# origin.net
KiCad netlist of a schematic drawn in Altium Designer
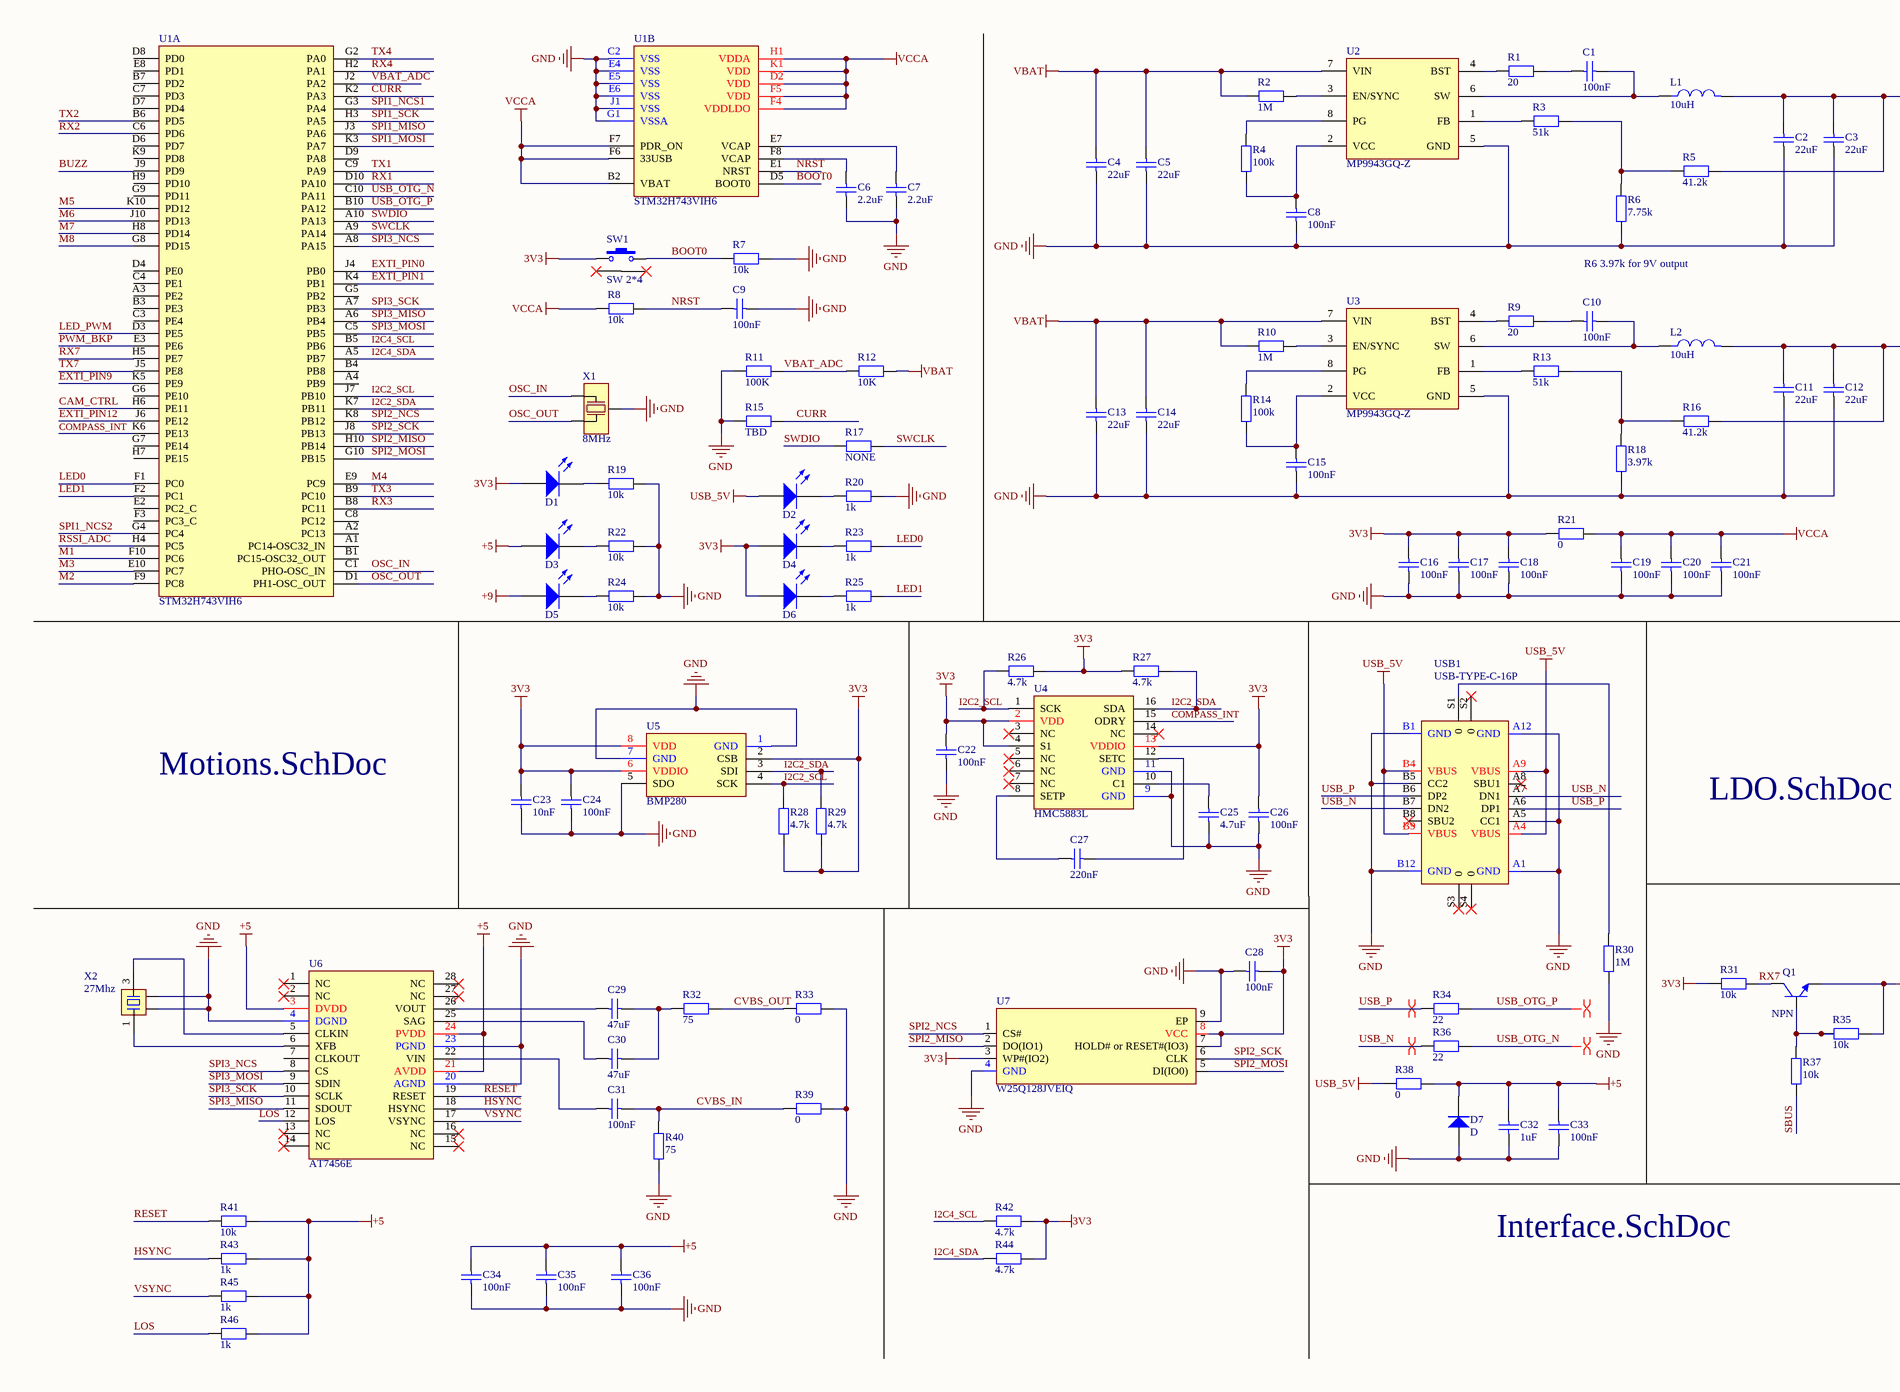
[diagram p0: origin.SchDoc, left]
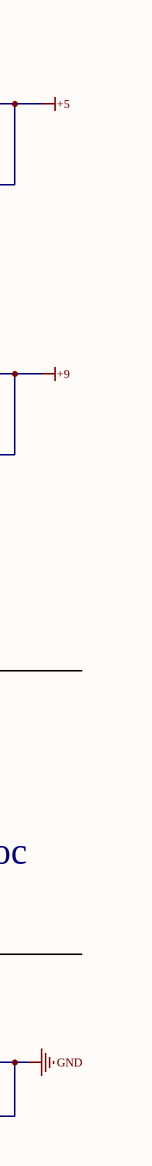
[diagram p1: origin.SchDoc, middle]

(export (version "E")
  (design (tool "Eeschema 10.0.6"))
  (components
    (comp (ref "C1")
      (value "100nF")
      (footprint "C0402_NS")
      (description "Capacitance 0402")
      (libsource (lib "AxisQuad Components Lib") (part "C0402"))
    )
    (comp (ref "C2")
      (value "22uF")
      (footprint "C1206_NS")
      (description "Capacitance 1206")
      (libsource (lib "AxisQuad Components Lib") (part "C1206"))
    )
    (comp (ref "C3")
      (value "22uF")
      (footprint "C1206_NS")
      (description "Capacitance 1206")
      (libsource (lib "AxisQuad Components Lib") (part "C1206"))
    )
    (comp (ref "C4")
      (value "22uF")
      (footprint "C1206_NS")
      (description "Capacitance 1206")
      (libsource (lib "AxisQuad Components Lib") (part "C1206"))
    )
    (comp (ref "C5")
      (value "22uF")
      (footprint "C1206_NS")
      (description "Capacitance 1206")
      (libsource (lib "AxisQuad Components Lib") (part "C1206"))
    )
    (comp (ref "C6")
      (value "2.2uF")
      (footprint "C0402_NS")
      (description "Capacitance 0402")
      (libsource (lib "AxisQuad Components Lib") (part "C0402"))
    )
    (comp (ref "C7")
      (value "2.2uF")
      (footprint "C0402_NS")
      (description "Capacitance 0402")
      (libsource (lib "AxisQuad Components Lib") (part "C0402"))
    )
    (comp (ref "C8")
      (value "100nF")
      (footprint "C0402_NS")
      (description "Capacitance 0402")
      (libsource (lib "AxisQuad Components Lib") (part "C0402"))
    )
    (comp (ref "C9")
      (value "100nF")
      (footprint "C0402_NS")
      (description "Capacitance 0402")
      (libsource (lib "AxisQuad Components Lib") (part "C0402"))
    )
    (comp (ref "C10")
      (value "100nF")
      (footprint "C0402_NS")
      (description "Capacitance 0402")
      (libsource (lib "AxisQuad Components Lib") (part "C0402"))
    )
    (comp (ref "C11")
      (value "22uF")
      (footprint "C1206_NS")
      (description "Capacitance 1206")
      (libsource (lib "AxisQuad Components Lib") (part "C1206"))
    )
    (comp (ref "C12")
      (value "22uF")
      (footprint "C1206_NS")
      (description "Capacitance 1206")
      (libsource (lib "AxisQuad Components Lib") (part "C1206"))
    )
    (comp (ref "C13")
      (value "22uF")
      (footprint "C1206_NS")
      (description "Capacitance 1206")
      (libsource (lib "AxisQuad Components Lib") (part "C1206"))
    )
    (comp (ref "C14")
      (value "22uF")
      (footprint "C1206_NS")
      (description "Capacitance 1206")
      (libsource (lib "AxisQuad Components Lib") (part "C1206"))
    )
    (comp (ref "C15")
      (value "100nF")
      (footprint "C0402_NS")
      (description "Capacitance 0402")
      (libsource (lib "AxisQuad Components Lib") (part "C0402"))
    )
    (comp (ref "C16")
      (value "100nF")
      (footprint "C0402_NS")
      (description "Capacitance 0402")
      (libsource (lib "AxisQuad Components Lib") (part "C0402"))
    )
    (comp (ref "C17")
      (value "100nF")
      (footprint "C0402_NS")
      (description "Capacitance 0402")
      (libsource (lib "AxisQuad Components Lib") (part "C0402"))
    )
    (comp (ref "C18")
      (value "100nF")
      (footprint "C0402_NS")
      (description "Capacitance 0402")
      (libsource (lib "AxisQuad Components Lib") (part "C0402"))
    )
    (comp (ref "C19")
      (value "100nF")
      (footprint "C0402_NS")
      (description "Capacitance 0402")
      (libsource (lib "AxisQuad Components Lib") (part "C0402"))
    )
    (comp (ref "C20")
      (value "100nF")
      (footprint "C0402_NS")
      (description "Capacitance 0402")
      (libsource (lib "AxisQuad Components Lib") (part "C0402"))
    )
    (comp (ref "C21")
      (value "100nF")
      (footprint "C0402_NS")
      (description "Capacitance 0402")
      (libsource (lib "AxisQuad Components Lib") (part "C0402"))
    )
    (comp (ref "C22")
      (value "100nF")
      (footprint "C0402_NS")
      (description "Capacitance 0402")
      (libsource (lib "AxisQuad Components Lib") (part "C0402"))
    )
    (comp (ref "C23")
      (value "10nF")
      (footprint "C0402_NS")
      (description "Capacitance 0402")
      (libsource (lib "AxisQuad Components Lib") (part "C0402"))
    )
    (comp (ref "C24")
      (value "100nF")
      (footprint "C0402_NS")
      (description "Capacitance 0402")
      (libsource (lib "AxisQuad Components Lib") (part "C0402"))
    )
    (comp (ref "C25")
      (value "4.7uF")
      (footprint "C0402_NS")
      (description "Capacitance 0402")
      (libsource (lib "AxisQuad Components Lib") (part "C0402"))
    )
    (comp (ref "C26")
      (value "100nF")
      (footprint "C0402_NS")
      (description "Capacitance 0402")
      (libsource (lib "AxisQuad Components Lib") (part "C0402"))
    )
    (comp (ref "C27")
      (value "220nF")
      (footprint "C0402_NS")
      (description "Capacitance 0402")
      (libsource (lib "AxisQuad Components Lib") (part "C0402"))
    )
    (comp (ref "C28")
      (value "100nF")
      (footprint "C0402_NS")
      (description "Capacitance 0402")
      (libsource (lib "AxisQuad Components Lib") (part "C0402"))
    )
    (comp (ref "C29")
      (value "47uF")
      (footprint "C_3528")
      (libsource (lib "AxisQuad Components Lib") (part "C"))
    )
    (comp (ref "C30")
      (value "47uF")
      (footprint "C_3528")
      (libsource (lib "AxisQuad Components Lib") (part "C"))
    )
    (comp (ref "C31")
      (value "100nF")
      (footprint "C0805_NS")
      (description "Capacitance 0805")
      (libsource (lib "AxisQuad Components Lib") (part "C0805"))
    )
    (comp (ref "C32")
      (value "1uF")
      (footprint "C0402_NS")
      (description "Capacitance 0402")
      (libsource (lib "AxisQuad Components Lib") (part "C0402"))
    )
    (comp (ref "C33")
      (value "100nF")
      (footprint "C0402_NS")
      (description "Capacitance 0402")
      (libsource (lib "AxisQuad Components Lib") (part "C0402"))
    )
    (comp (ref "C34")
      (value "100nF")
      (footprint "C0402_NS")
      (description "Capacitance 0402")
      (libsource (lib "AxisQuad Components Lib") (part "C0402"))
    )
    (comp (ref "C35")
      (value "100nF")
      (footprint "C0402_NS")
      (description "Capacitance 0402")
      (libsource (lib "AxisQuad Components Lib") (part "C0402"))
    )
    (comp (ref "C36")
      (value "100nF")
      (footprint "C0402_NS")
      (description "Capacitance 0402")
      (libsource (lib "AxisQuad Components Lib") (part "C0402"))
    )
    (comp (ref "D1")
      (value "LED")
      (footprint "LED0402-B")
      (description "发光二极管")
      (libsource (lib "AxisQuad Components Lib") (part "LED0402"))
    )
    (comp (ref "D2")
      (value "LED")
      (footprint "LED0402-B")
      (description "发光二极管")
      (libsource (lib "AxisQuad Components Lib") (part "LED0402"))
    )
    (comp (ref "D3")
      (value "LED")
      (footprint "LED0402-B")
      (description "发光二极管")
      (libsource (lib "AxisQuad Components Lib") (part "LED0402"))
    )
    (comp (ref "D4")
      (value "LED")
      (footprint "LED0402-B")
      (description "发光二极管")
      (libsource (lib "AxisQuad Components Lib") (part "LED0402"))
    )
    (comp (ref "D5")
      (value "LED")
      (footprint "LED0402-B")
      (description "发光二极管")
      (libsource (lib "AxisQuad Components Lib") (part "LED0402"))
    )
    (comp (ref "D6")
      (value "LED")
      (footprint "LED0402-B")
      (description "发光二极管")
      (libsource (lib "AxisQuad Components Lib") (part "LED0402"))
    )
    (comp (ref "D7") (value "D") (footprint "SOD-123") (libsource (lib "AxisQuad Components Lib") (part "D")))
    (comp (ref "L1") (value "10uH") (footprint "IHLP2020") (libsource (lib "DBS Components Lib") (part "L")))
    (comp (ref "L2") (value "10uH") (footprint "IHLP2020") (libsource (lib "DBS Components Lib") (part "L")))
    (comp (ref "Q1")
      (value "NPN")
      (footprint "SOT23-3")
      (description "NPN三极管")
      (libsource (lib "AxisQuad Components Lib") (part "NPN"))
    )
    (comp (ref "R1")
      (value "20")
      (footprint "R0402_NS")
      (description "Resistance 0402")
      (libsource (lib "AxisQuad Components Lib") (part "R0402"))
    )
    (comp (ref "R2")
      (value "1M")
      (footprint "R0402_NS")
      (description "Resistance 0402")
      (libsource (lib "AxisQuad Components Lib") (part "R0402"))
    )
    (comp (ref "R3")
      (value "51k")
      (footprint "R0402_NS")
      (description "Resistance 0402")
      (libsource (lib "AxisQuad Components Lib") (part "R0402"))
    )
    (comp (ref "R4")
      (value "100k")
      (footprint "R0402_NS")
      (description "Resistance 0402")
      (libsource (lib "AxisQuad Components Lib") (part "R0402"))
    )
    (comp (ref "R5")
      (value "41.2k")
      (footprint "R0402_NS")
      (description "Resistance 0402")
      (libsource (lib "AxisQuad Components Lib") (part "R0402"))
    )
    (comp (ref "R6")
      (value "7.75k")
      (footprint "R0402_NS")
      (description "Resistance 0402")
      (libsource (lib "AxisQuad Components Lib") (part "R0402"))
    )
    (comp (ref "R7")
      (value "10k")
      (footprint "R0402_NS")
      (description "Resistance 0402")
      (libsource (lib "AxisQuad Components Lib") (part "R0402"))
    )
    (comp (ref "R8")
      (value "10k")
      (footprint "R0402_NS")
      (description "Resistance 0402")
      (libsource (lib "AxisQuad Components Lib") (part "R0402"))
    )
    (comp (ref "R9")
      (value "20")
      (footprint "R0402_NS")
      (description "Resistance 0402")
      (libsource (lib "AxisQuad Components Lib") (part "R0402"))
    )
    (comp (ref "R10")
      (value "1M")
      (footprint "R0402_NS")
      (description "Resistance 0402")
      (libsource (lib "AxisQuad Components Lib") (part "R0402"))
    )
    (comp (ref "R11")
      (value "100K")
      (footprint "R0402_NS")
      (description "Resistance 0402")
      (libsource (lib "AxisQuad Components Lib") (part "R0402"))
    )
    (comp (ref "R12")
      (value "10K")
      (footprint "R0402_NS")
      (description "Resistance 0402")
      (libsource (lib "AxisQuad Components Lib") (part "R0402"))
    )
    (comp (ref "R13")
      (value "51k")
      (footprint "R0402_NS")
      (description "Resistance 0402")
      (libsource (lib "AxisQuad Components Lib") (part "R0402"))
    )
    (comp (ref "R14")
      (value "100k")
      (footprint "R0402_NS")
      (description "Resistance 0402")
      (libsource (lib "AxisQuad Components Lib") (part "R0402"))
    )
    (comp (ref "R15")
      (value "TBD")
      (footprint "R0603_NS")
      (description "Resistance 0603")
      (libsource (lib "DBS Components Lib") (part "R0603"))
    )
    (comp (ref "R16")
      (value "41.2k")
      (footprint "R0402_NS")
      (description "Resistance 0402")
      (libsource (lib "AxisQuad Components Lib") (part "R0402"))
    )
    (comp (ref "R17")
      (value "NONE")
      (footprint "R0402_NS")
      (description "Resistance 0402")
      (libsource (lib "AxisQuad Components Lib") (part "R0402"))
    )
    (comp (ref "R18")
      (value "3.97k")
      (footprint "R0402_NS")
      (description "Resistance 0402")
      (libsource (lib "AxisQuad Components Lib") (part "R0402"))
    )
    (comp (ref "R19")
      (value "10k")
      (footprint "R0402_NS")
      (description "Resistance 0402")
      (libsource (lib "AxisQuad Components Lib") (part "R0402"))
    )
    (comp (ref "R20")
      (value "1k")
      (footprint "R0402_NS")
      (description "Resistance 0402")
      (libsource (lib "AxisQuad Components Lib") (part "R0402"))
    )
    (comp (ref "R21")
      (value "0")
      (footprint "R0402_NS")
      (description "Resistance 0402")
      (libsource (lib "AxisQuad Components Lib") (part "R0402"))
    )
    (comp (ref "R22")
      (value "10k")
      (footprint "R0402_NS")
      (description "Resistance 0402")
      (libsource (lib "AxisQuad Components Lib") (part "R0402"))
    )
    (comp (ref "R23")
      (value "1k")
      (footprint "R0402_NS")
      (description "Resistance 0402")
      (libsource (lib "AxisQuad Components Lib") (part "R0402"))
    )
    (comp (ref "R24")
      (value "10k")
      (footprint "R0402_NS")
      (description "Resistance 0402")
      (libsource (lib "AxisQuad Components Lib") (part "R0402"))
    )
    (comp (ref "R25")
      (value "1k")
      (footprint "R0402_NS")
      (description "Resistance 0402")
      (libsource (lib "AxisQuad Components Lib") (part "R0402"))
    )
    (comp (ref "R26")
      (value "4.7k")
      (footprint "R0402_NS")
      (description "Resistance 0402")
      (libsource (lib "AxisQuad Components Lib") (part "R0402"))
    )
    (comp (ref "R27")
      (value "4.7k")
      (footprint "R0402_NS")
      (description "Resistance 0402")
      (libsource (lib "AxisQuad Components Lib") (part "R0402"))
    )
    (comp (ref "R28")
      (value "4.7k")
      (footprint "R0402_NS")
      (description "Resistance 0402")
      (libsource (lib "AxisQuad Components Lib") (part "R0402"))
    )
    (comp (ref "R29")
      (value "4.7k")
      (footprint "R0402_NS")
      (description "Resistance 0402")
      (libsource (lib "AxisQuad Components Lib") (part "R0402"))
    )
    (comp (ref "R30")
      (value "1M")
      (footprint "R0402_NS")
      (description "Resistance 0402")
      (libsource (lib "AxisQuad Components Lib") (part "R0402"))
    )
    (comp (ref "R31")
      (value "10k")
      (footprint "R0402_NS")
      (description "Resistance 0402")
      (libsource (lib "AxisQuad Components Lib") (part "R0402"))
    )
    (comp (ref "R32")
      (value "75")
      (footprint "R0402_NS")
      (description "Resistance 0402")
      (libsource (lib "AxisQuad Components Lib") (part "R0402"))
    )
    (comp (ref "R33")
      (value "0")
      (footprint "R0402_NS")
      (description "Resistance 0402")
      (libsource (lib "AxisQuad Components Lib") (part "R0402"))
    )
    (comp (ref "R34")
      (value "22")
      (footprint "R0402_NS")
      (description "Resistance 0402")
      (libsource (lib "AxisQuad Components Lib") (part "R0402"))
    )
    (comp (ref "R35")
      (value "10k")
      (footprint "R0402_NS")
      (description "Resistance 0402")
      (libsource (lib "AxisQuad Components Lib") (part "R0402"))
    )
    (comp (ref "R36")
      (value "22")
      (footprint "R0402_NS")
      (description "Resistance 0402")
      (libsource (lib "AxisQuad Components Lib") (part "R0402"))
    )
    (comp (ref "R37")
      (value "10k")
      (footprint "R0402_NS")
      (description "Resistance 0402")
      (libsource (lib "AxisQuad Components Lib") (part "R0402"))
    )
    (comp (ref "R38")
      (value "0")
      (footprint "R0603_NS")
      (description "Resistance 0603")
      (libsource (lib "DBS Components Lib") (part "R0603"))
    )
    (comp (ref "R39")
      (value "0")
      (footprint "R0402_NS")
      (description "Resistance 0402")
      (libsource (lib "AxisQuad Components Lib") (part "R0402"))
    )
    (comp (ref "R40")
      (value "75")
      (footprint "R0402_NS")
      (description "Resistance 0402")
      (libsource (lib "AxisQuad Components Lib") (part "R0402"))
    )
    (comp (ref "R41")
      (value "10k")
      (footprint "R0402_NS")
      (description "Resistance 0402")
      (libsource (lib "AxisQuad Components Lib") (part "R0402"))
    )
    (comp (ref "R42")
      (value "4.7k")
      (footprint "R0402_NS")
      (description "Resistance 0402")
      (libsource (lib "AxisQuad Components Lib") (part "R0402"))
    )
    (comp (ref "R43")
      (value "1k")
      (footprint "R0402_NS")
      (description "Resistance 0402")
      (libsource (lib "AxisQuad Components Lib") (part "R0402"))
    )
    (comp (ref "R44")
      (value "4.7k")
      (footprint "R0402_NS")
      (description "Resistance 0402")
      (libsource (lib "AxisQuad Components Lib") (part "R0402"))
    )
    (comp (ref "R45")
      (value "1k")
      (footprint "R0402_NS")
      (description "Resistance 0402")
      (libsource (lib "AxisQuad Components Lib") (part "R0402"))
    )
    (comp (ref "R46")
      (value "1k")
      (footprint "R0402_NS")
      (description "Resistance 0402")
      (libsource (lib "AxisQuad Components Lib") (part "R0402"))
    )
    (comp (ref "SW1")
      (value "SW 2*4")
      (footprint "SW2*4")
      (description "2*4 双进轻触开关")
      (libsource (lib "DBS Components Lib") (part "SW 2*4"))
    )
    (comp (ref "U1")
      (value "STM32H743VIH6")
      (footprint "TFBGA100")
      (description "480MHz BGA100 MCU")
      (libsource (lib "Daedalus Components Lib") (part "STM32H743VIH6"))
    )
    (comp (ref "U2")
      (value "MP9943GQ-Z")
      (footprint "DFN-8")
      (description "High Efficiency 3A Peak, 36V, Synchronous Step Down Converter With Power Good")
      (libsource (lib "AxisQuad Components Lib") (part "MP9943GQ-Z"))
    )
    (comp (ref "U3")
      (value "MP9943GQ-Z")
      (footprint "DFN-8")
      (description "High Efficiency 3A Peak, 36V, Synchronous Step Down Converter With Power Good")
      (libsource (lib "AxisQuad Components Lib") (part "MP9943GQ-Z"))
    )
    (comp (ref "U4")
      (value "HMC5883L")
      (footprint "LGA-16")
      (description "Compass, Pin-Pin with QMC5883L")
      (libsource (lib "AxisQuad Components Lib") (part "HMC5883L"))
    )
    (comp (ref "U5")
      (value "BMP280")
      (footprint "LGA-8-BMP280")
      (description "BOSCH Barometer")
      (libsource (lib "AxisQuad Components Lib") (part "BMP280"))
    )
    (comp (ref "U6")
      (value "AT7456E")
      (footprint "TSSOP28")
      (description "中科微电子 Character Overlay Chip")
      (libsource (lib "Daedalus Components Lib") (part "AT7456E"))
    )
    (comp (ref "U7")
      (value "W25Q128JVEIQ")
      (footprint "WSON-8")
      (description "16M SPI Flash WSON-8")
      (libsource (lib "Daedalus Components Lib") (part "W25Q128JVEIQ"))
    )
    (comp (ref "USB1")
      (value "USB-TYPE-C-16P")
      (footprint "USB-C-SMD_16P")
      (description "TYPE-C USB Male Interface DIP")
      (libsource (lib "DBS Components Lib") (part "USB-TYPE-C-16P"))
    )
    (comp (ref "X1")
      (value "8MHz")
      (footprint "OSC-SMD-3")
      (description "3213 Crystal")
      (libsource (lib "AxisQuad Components Lib") (part "Crystal 3P 3213"))
    )
    (comp (ref "X2")
      (value "27Mhz")
      (footprint "XTAL-2025-4P")
      (description "4脚无源晶振(谐振器）")
      (libsource (lib "AxisQuad Components Lib") (part "Crystal 4P"))
    )
  )
  (nets
    (net (code "1") (name "+5") (class "Default")
      (node (ref "C2") (pin "2") (pinfunction "2_2") (pintype "passive"))
      (node (ref "C3") (pin "2") (pinfunction "2_2") (pintype "passive"))
      (node (ref "C32") (pin "1") (pinfunction "1_1") (pintype "passive"))
      (node (ref "C33") (pin "1") (pinfunction "1_1") (pintype "passive"))
      (node (ref "C34") (pin "1") (pinfunction "1_1") (pintype "passive"))
      (node (ref "C35") (pin "1") (pinfunction "1_1") (pintype "passive"))
      (node (ref "C36") (pin "1") (pinfunction "1_1") (pintype "passive"))
      (node (ref "D3") (pin "1") (pinfunction "A_1") (pintype "passive"))
      (node (ref "D7") (pin "2") (pinfunction "K_2") (pintype "passive"))
      (node (ref "L1") (pin "2") (pinfunction "2_2") (pintype "passive"))
      (node (ref "R38") (pin "2") (pinfunction "2_2") (pintype "passive"))
      (node (ref "R41") (pin "2") (pinfunction "2_2") (pintype "passive"))
      (node (ref "R43") (pin "2") (pinfunction "2_2") (pintype "passive"))
      (node (ref "R45") (pin "2") (pinfunction "2_2") (pintype "passive"))
      (node (ref "R46") (pin "2") (pinfunction "2_2") (pintype "passive"))
      (node (ref "R5") (pin "1") (pinfunction "1_1") (pintype "passive"))
      (node (ref "U6") (pin "21") (pinfunction "AVDD_21") (pintype "passive"))
      (node (ref "U6") (pin "24") (pinfunction "PVDD_24") (pintype "passive"))
      (node (ref "U6") (pin "3") (pinfunction "DVDD_3") (pintype "passive"))
    )
    (net (code "2") (name "+9") (class "Default")
      (node (ref "C11") (pin "2") (pinfunction "2_2") (pintype "passive"))
      (node (ref "C12") (pin "2") (pinfunction "2_2") (pintype "passive"))
      (node (ref "D5") (pin "1") (pinfunction "A_1") (pintype "passive"))
      (node (ref "L2") (pin "2") (pinfunction "2_2") (pintype "passive"))
      (node (ref "R16") (pin "1") (pinfunction "1_1") (pintype "passive"))
    )
    (net (code "4") (name "/BOOT0") (class "Default")
      (node (ref "R7") (pin "1") (pinfunction "1_1") (pintype "passive"))
      (node (ref "SW1") (pin "2") (pinfunction "2_2") (pintype "passive"))
      (node (ref "U1") (pin "D5") (pinfunction "BOOT0_D5") (pintype "passive"))
    )
    (net (code "5") (name "/BUZZ") (class "Default")
      (node (ref "U1") (pin "J9") (pinfunction "PD9_J9") (pintype "passive"))
    )
    (net (code "6") (name "/CAM_CTRL") (class "Default")
      (node (ref "U1") (pin "H6") (pinfunction "PE11_H6") (pintype "passive"))
    )
    (net (code "7") (name "/COMPASS_INT") (class "Default")
      (node (ref "U1") (pin "K6") (pinfunction "PE13_K6") (pintype "passive"))
      (node (ref "U4") (pin "15") (pinfunction "ODRY_15") (pintype "passive"))
    )
    (net (code "8") (name "/CURR") (class "Default")
      (node (ref "R15") (pin "2") (pinfunction "2_2") (pintype "passive"))
      (node (ref "U1") (pin "K2") (pinfunction "PA3_K2") (pintype "passive"))
    )
    (net (code "9") (name "/CVBS_IN") (class "Default")
      (node (ref "C31") (pin "2") (pinfunction "2_2") (pintype "passive"))
      (node (ref "R39") (pin "2") (pinfunction "2_2") (pintype "passive"))
      (node (ref "R40") (pin "2") (pinfunction "2_2") (pintype "passive"))
    )
    (net (code "10") (name "/CVBS_OUT") (class "Default")
      (node (ref "R32") (pin "2") (pinfunction "2_2") (pintype "passive"))
      (node (ref "R33") (pin "1") (pinfunction "1_1") (pintype "passive"))
    )
    (net (code "11") (name "/EXTI_PIN0") (class "Default")
      (node (ref "U1") (pin "J4") (pinfunction "PB0_J4") (pintype "passive"))
    )
    (net (code "12") (name "/EXTI_PIN1") (class "Default")
      (node (ref "U1") (pin "K4") (pinfunction "PB1_K4") (pintype "passive"))
    )
    (net (code "13") (name "/EXTI_PIN9") (class "Default")
      (node (ref "U1") (pin "K5") (pinfunction "PE9_K5") (pintype "passive"))
    )
    (net (code "14") (name "/EXTI_PIN12") (class "Default")
      (node (ref "U1") (pin "J6") (pinfunction "PE12_J6") (pintype "passive"))
    )
    (net (code "15") (name "/HSYNC") (class "Default")
      (node (ref "R43") (pin "1") (pinfunction "1_1") (pintype "passive"))
      (node (ref "U6") (pin "18") (pinfunction "HSYNC_18") (pintype "passive"))
    )
    (net (code "16") (name "/I2C2_SCL") (class "Default")
      (node (ref "R26") (pin "2") (pinfunction "2_2") (pintype "passive"))
      (node (ref "R28") (pin "1") (pinfunction "1_1") (pintype "passive"))
      (node (ref "U1") (pin "J7") (pinfunction "PB10_J7") (pintype "passive"))
      (node (ref "U4") (pin "1") (pinfunction "SCK_1") (pintype "passive"))
      (node (ref "U5") (pin "4") (pinfunction "SCK_4") (pintype "passive"))
    )
    (net (code "17") (name "/I2C2_SDA") (class "Default")
      (node (ref "R27") (pin "1") (pinfunction "1_1") (pintype "passive"))
      (node (ref "R29") (pin "1") (pinfunction "1_1") (pintype "passive"))
      (node (ref "U1") (pin "K7") (pinfunction "PB11_K7") (pintype "passive"))
      (node (ref "U4") (pin "16") (pinfunction "SDA_16") (pintype "passive"))
      (node (ref "U5") (pin "3") (pinfunction "SDI_3") (pintype "passive"))
    )
    (net (code "18") (name "/I2C4_SCL") (class "Default")
      (node (ref "R42") (pin "1") (pinfunction "1_1") (pintype "passive"))
      (node (ref "U1") (pin "B5") (pinfunction "PB6_B5") (pintype "passive"))
    )
    (net (code "19") (name "/I2C4_SDA") (class "Default")
      (node (ref "R44") (pin "1") (pinfunction "1_1") (pintype "passive"))
      (node (ref "U1") (pin "A5") (pinfunction "PB7_A5") (pintype "passive"))
    )
    (net (code "20") (name "/LED0") (class "Default")
      (node (ref "R23") (pin "2") (pinfunction "2_2") (pintype "passive"))
      (node (ref "U1") (pin "F1") (pinfunction "PC0_F1") (pintype "passive"))
    )
    (net (code "21") (name "/LED1") (class "Default")
      (node (ref "R25") (pin "2") (pinfunction "2_2") (pintype "passive"))
      (node (ref "U1") (pin "F2") (pinfunction "PC1_F2") (pintype "passive"))
    )
    (net (code "22") (name "/LED_PWM") (class "Default")
      (node (ref "U1") (pin "D3") (pinfunction "PE5_D3") (pintype "passive"))
    )
    (net (code "23") (name "/LOS") (class "Default")
      (node (ref "R46") (pin "1") (pinfunction "1_1") (pintype "passive"))
      (node (ref "U6") (pin "12") (pinfunction "LOS_12") (pintype "passive"))
    )
    (net (code "24") (name "/M1") (class "Default")
      (node (ref "U1") (pin "F10") (pinfunction "PC6_F10") (pintype "passive"))
    )
    (net (code "25") (name "/M2") (class "Default")
      (node (ref "U1") (pin "F9") (pinfunction "PC8_F9") (pintype "passive"))
    )
    (net (code "26") (name "/M3") (class "Default")
      (node (ref "U1") (pin "E10") (pinfunction "PC7_E10") (pintype "passive"))
    )
    (net (code "27") (name "/M4") (class "Default")
      (node (ref "U1") (pin "E9") (pinfunction "PC9_E9") (pintype "passive"))
    )
    (net (code "28") (name "/M5") (class "Default")
      (node (ref "U1") (pin "K10") (pinfunction "PD12_K10") (pintype "passive"))
    )
    (net (code "29") (name "/M6") (class "Default")
      (node (ref "U1") (pin "J10") (pinfunction "PD13_J10") (pintype "passive"))
    )
    (net (code "30") (name "/M7") (class "Default")
      (node (ref "U1") (pin "H8") (pinfunction "PD14_H8") (pintype "passive"))
    )
    (net (code "31") (name "/M8") (class "Default")
      (node (ref "U1") (pin "G8") (pinfunction "PD15_G8") (pintype "passive"))
    )
    (net (code "32") (name "/NRST") (class "Default")
      (node (ref "C9") (pin "2") (pinfunction "2_2") (pintype "passive"))
      (node (ref "R8") (pin "2") (pinfunction "2_2") (pintype "passive"))
      (node (ref "U1") (pin "E1") (pinfunction "NRST_E1") (pintype "passive"))
    )
    (net (code "33") (name "/OSC_IN") (class "Default")
      (node (ref "U1") (pin "C1") (pinfunction "PHO-OSC_IN_C1") (pintype "passive"))
      (node (ref "X1") (pin "1") (pinfunction "OSC_IN_1") (pintype "passive"))
    )
    (net (code "34") (name "/OSC_OUT") (class "Default")
      (node (ref "U1") (pin "D1") (pinfunction "PH1-OSC_OUT_D1") (pintype "passive"))
      (node (ref "X1") (pin "3") (pinfunction "OSC_OUT_3") (pintype "passive"))
    )
    (net (code "35") (name "/PWM_BKP") (class "Default")
      (node (ref "U1") (pin "E3") (pinfunction "PE6_E3") (pintype "passive"))
    )
    (net (code "36") (name "/RESET") (class "Default")
      (node (ref "R41") (pin "1") (pinfunction "1_1") (pintype "passive"))
      (node (ref "U6") (pin "19") (pinfunction "RESET_19") (pintype "passive"))
    )
    (net (code "37") (name "/RSSI_ADC") (class "Default")
      (node (ref "U1") (pin "H4") (pinfunction "PC5_H4") (pintype "passive"))
    )
    (net (code "38") (name "/RX1") (class "Default")
      (node (ref "U1") (pin "D10") (pinfunction "PA10_D10") (pintype "passive"))
    )
    (net (code "39") (name "/RX2") (class "Default")
      (node (ref "U1") (pin "C6") (pinfunction "PD6_C6") (pintype "passive"))
    )
    (net (code "40") (name "/RX3") (class "Default")
      (node (ref "U1") (pin "B8") (pinfunction "PC11_B8") (pintype "passive"))
    )
    (net (code "41") (name "/RX4") (class "Default")
      (node (ref "U1") (pin "H2") (pinfunction "PA1_H2") (pintype "passive"))
    )
    (net (code "42") (name "/RX7") (class "Default")
      (node (ref "Q1") (pin "3") (pinfunction "C_3") (pintype "passive"))
      (node (ref "R31") (pin "1") (pinfunction "1_1") (pintype "passive"))
      (node (ref "U1") (pin "H5") (pinfunction "PE7_H5") (pintype "passive"))
    )
    (net (code "43") (name "/SBUS") (class "Default")
      (node (ref "R37") (pin "2") (pinfunction "2_2") (pintype "passive"))
    )
    (net (code "44") (name "/SPI1_MISO") (class "Default")
      (node (ref "U1") (pin "J3") (pinfunction "PA6_J3") (pintype "passive"))
    )
    (net (code "45") (name "/SPI1_MOSI") (class "Default")
      (node (ref "U1") (pin "K3") (pinfunction "PA7_K3") (pintype "passive"))
    )
    (net (code "46") (name "/SPI1_NCS1") (class "Default")
      (node (ref "U1") (pin "G3") (pinfunction "PA4_G3") (pintype "passive"))
    )
    (net (code "47") (name "/SPI1_NCS2") (class "Default")
      (node (ref "U1") (pin "G4") (pinfunction "PC4_G4") (pintype "passive"))
    )
    (net (code "48") (name "/SPI1_SCK") (class "Default")
      (node (ref "U1") (pin "H3") (pinfunction "PA5_H3") (pintype "passive"))
    )
    (net (code "49") (name "/SPI2_MISO") (class "Default")
      (node (ref "U1") (pin "H10") (pinfunction "PB14_H10") (pintype "passive"))
      (node (ref "U7") (pin "2") (pinfunction "DO(IO1)_2") (pintype "passive"))
    )
    (net (code "50") (name "/SPI2_MOSI") (class "Default")
      (node (ref "U1") (pin "G10") (pinfunction "PB15_G10") (pintype "passive"))
      (node (ref "U7") (pin "5") (pinfunction "DI(IO0)_5") (pintype "passive"))
    )
    (net (code "51") (name "/SPI2_NCS") (class "Default")
      (node (ref "U1") (pin "K8") (pinfunction "PB12_K8") (pintype "passive"))
      (node (ref "U7") (pin "1") (pinfunction "CS#_1") (pintype "passive"))
    )
    (net (code "52") (name "/SPI2_SCK") (class "Default")
      (node (ref "U1") (pin "J8") (pinfunction "PB13_J8") (pintype "passive"))
      (node (ref "U7") (pin "6") (pinfunction "CLK_6") (pintype "passive"))
    )
    (net (code "53") (name "/SPI3_MISO") (class "Default")
      (node (ref "U1") (pin "A6") (pinfunction "PB4_A6") (pintype "passive"))
      (node (ref "U6") (pin "11") (pinfunction "SDOUT_11") (pintype "passive"))
    )
    (net (code "54") (name "/SPI3_MOSI") (class "Default")
      (node (ref "U1") (pin "C5") (pinfunction "PB5_C5") (pintype "passive"))
      (node (ref "U6") (pin "9") (pinfunction "SDIN_9") (pintype "passive"))
    )
    (net (code "55") (name "/SPI3_NCS") (class "Default")
      (node (ref "U1") (pin "A8") (pinfunction "PA15_A8") (pintype "passive"))
      (node (ref "U6") (pin "8") (pinfunction "CS_8") (pintype "passive"))
    )
    (net (code "56") (name "/SPI3_SCK") (class "Default")
      (node (ref "U1") (pin "A7") (pinfunction "PB3_A7") (pintype "passive"))
      (node (ref "U6") (pin "10") (pinfunction "SCLK_10") (pintype "passive"))
    )
    (net (code "57") (name "/SWCLK") (class "Default")
      (node (ref "R17") (pin "1") (pinfunction "1_1") (pintype "passive"))
      (node (ref "U1") (pin "A9") (pinfunction "PA14_A9") (pintype "passive"))
    )
    (net (code "58") (name "/SWDIO") (class "Default")
      (node (ref "R17") (pin "2") (pinfunction "2_2") (pintype "passive"))
      (node (ref "U1") (pin "A10") (pinfunction "PA13_A10") (pintype "passive"))
    )
    (net (code "59") (name "/TX1") (class "Default")
      (node (ref "U1") (pin "C9") (pinfunction "PA9_C9") (pintype "passive"))
    )
    (net (code "60") (name "/TX2") (class "Default")
      (node (ref "U1") (pin "B6") (pinfunction "PD5_B6") (pintype "passive"))
    )
    (net (code "61") (name "/TX3") (class "Default")
      (node (ref "U1") (pin "B9") (pinfunction "PC10_B9") (pintype "passive"))
    )
    (net (code "62") (name "/TX4") (class "Default")
      (node (ref "U1") (pin "G2") (pinfunction "PA0_G2") (pintype "passive"))
    )
    (net (code "63") (name "/TX7") (class "Default")
      (node (ref "U1") (pin "J5") (pinfunction "PE8_J5") (pintype "passive"))
    )
    (net (code "64") (name "/USB_N") (class "Default")
      (node (ref "R36") (pin "2") (pinfunction "2_2") (pintype "passive"))
      (node (ref "USB1") (pin "A7") (pinfunction "DN1_A7") (pintype "passive"))
      (node (ref "USB1") (pin "B7") (pinfunction "DN2_B7") (pintype "passive"))
    )
    (net (code "65") (name "/USB_OTG_N") (class "Default")
      (node (ref "R36") (pin "1") (pinfunction "1_1") (pintype "passive"))
      (node (ref "U1") (pin "C10") (pinfunction "PA11_C10") (pintype "passive"))
    )
    (net (code "66") (name "/USB_OTG_P") (class "Default")
      (node (ref "R34") (pin "1") (pinfunction "1_1") (pintype "passive"))
      (node (ref "U1") (pin "B10") (pinfunction "PA12_B10") (pintype "passive"))
    )
    (net (code "67") (name "/USB_P") (class "Default")
      (node (ref "R34") (pin "2") (pinfunction "2_2") (pintype "passive"))
      (node (ref "USB1") (pin "A6") (pinfunction "DP1_A6") (pintype "passive"))
      (node (ref "USB1") (pin "B6") (pinfunction "DP2_B6") (pintype "passive"))
    )
    (net (code "68") (name "/VBAT_ADC") (class "Default")
      (node (ref "R11") (pin "2") (pinfunction "2_2") (pintype "passive"))
      (node (ref "R12") (pin "1") (pinfunction "1_1") (pintype "passive"))
      (node (ref "U1") (pin "J2") (pinfunction "PA2_J2") (pintype "passive"))
    )
    (net (code "69") (name "/VSYNC") (class "Default")
      (node (ref "R45") (pin "1") (pinfunction "1_1") (pintype "passive"))
      (node (ref "U6") (pin "17") (pinfunction "VSYNC_17") (pintype "passive"))
    )
    (net (code "70") (name "3V3") (class "Default")
      (node (ref "C16") (pin "1") (pinfunction "1_1") (pintype "passive"))
      (node (ref "C17") (pin "1") (pinfunction "1_1") (pintype "passive"))
      (node (ref "C18") (pin "1") (pinfunction "1_1") (pintype "passive"))
      (node (ref "C22") (pin "1") (pinfunction "1_1") (pintype "passive"))
      (node (ref "C23") (pin "1") (pinfunction "1_1") (pintype "passive"))
      (node (ref "C24") (pin "1") (pinfunction "1_1") (pintype "passive"))
      (node (ref "C26") (pin "1") (pinfunction "1_1") (pintype "passive"))
      (node (ref "C28") (pin "2") (pinfunction "2_2") (pintype "passive"))
      (node (ref "D1") (pin "1") (pinfunction "A_1") (pintype "passive"))
      (node (ref "D4") (pin "1") (pinfunction "A_1") (pintype "passive"))
      (node (ref "D6") (pin "1") (pinfunction "A_1") (pintype "passive"))
      (node (ref "R21") (pin "1") (pinfunction "1_1") (pintype "passive"))
      (node (ref "R26") (pin "1") (pinfunction "1_1") (pintype "passive"))
      (node (ref "R27") (pin "2") (pinfunction "2_2") (pintype "passive"))
      (node (ref "R28") (pin "2") (pinfunction "2_2") (pintype "passive"))
      (node (ref "R29") (pin "2") (pinfunction "2_2") (pintype "passive"))
      (node (ref "R31") (pin "2") (pinfunction "2_2") (pintype "passive"))
      (node (ref "R42") (pin "2") (pinfunction "2_2") (pintype "passive"))
      (node (ref "R44") (pin "2") (pinfunction "2_2") (pintype "passive"))
      (node (ref "SW1") (pin "1") (pinfunction "1_1") (pintype "passive"))
      (node (ref "U4") (pin "13") (pinfunction "VDDIO_13") (pintype "passive"))
      (node (ref "U4") (pin "2") (pinfunction "VDD_2") (pintype "passive"))
      (node (ref "U4") (pin "4") (pinfunction "S1_4") (pintype "passive"))
      (node (ref "U5") (pin "2") (pinfunction "CSB_2") (pintype "passive"))
      (node (ref "U5") (pin "6") (pinfunction "VDDIO_6") (pintype "passive"))
      (node (ref "U5") (pin "8") (pinfunction "VDD_8") (pintype "passive"))
      (node (ref "U7") (pin "3") (pinfunction "WP#(IO2)_3") (pintype "passive"))
      (node (ref "U7") (pin "7") (pinfunction "HOLD#_or_RESET#(IO3)_7") (pintype "passive"))
      (node (ref "U7") (pin "8") (pinfunction "VCC_8") (pintype "passive"))
    )
    (net (code "71") (name "GND") (class "Default")
      (node (ref "C11") (pin "1") (pinfunction "1_1") (pintype "passive"))
      (node (ref "C12") (pin "1") (pinfunction "1_1") (pintype "passive"))
      (node (ref "C13") (pin "1") (pinfunction "1_1") (pintype "passive"))
      (node (ref "C14") (pin "1") (pinfunction "1_1") (pintype "passive"))
      (node (ref "C15") (pin "1") (pinfunction "1_1") (pintype "passive"))
      (node (ref "C16") (pin "2") (pinfunction "2_2") (pintype "passive"))
      (node (ref "C17") (pin "2") (pinfunction "2_2") (pintype "passive"))
      (node (ref "C18") (pin "2") (pinfunction "2_2") (pintype "passive"))
      (node (ref "C19") (pin "2") (pinfunction "2_2") (pintype "passive"))
      (node (ref "C2") (pin "1") (pinfunction "1_1") (pintype "passive"))
      (node (ref "C20") (pin "2") (pinfunction "2_2") (pintype "passive"))
      (node (ref "C21") (pin "2") (pinfunction "2_2") (pintype "passive"))
      (node (ref "C22") (pin "2") (pinfunction "2_2") (pintype "passive"))
      (node (ref "C23") (pin "2") (pinfunction "2_2") (pintype "passive"))
      (node (ref "C24") (pin "2") (pinfunction "2_2") (pintype "passive"))
      (node (ref "C25") (pin "2") (pinfunction "2_2") (pintype "passive"))
      (node (ref "C26") (pin "2") (pinfunction "2_2") (pintype "passive"))
      (node (ref "C28") (pin "1") (pinfunction "1_1") (pintype "passive"))
      (node (ref "C3") (pin "1") (pinfunction "1_1") (pintype "passive"))
      (node (ref "C32") (pin "2") (pinfunction "2_2") (pintype "passive"))
      (node (ref "C33") (pin "2") (pinfunction "2_2") (pintype "passive"))
      (node (ref "C34") (pin "2") (pinfunction "2_2") (pintype "passive"))
      (node (ref "C35") (pin "2") (pinfunction "2_2") (pintype "passive"))
      (node (ref "C36") (pin "2") (pinfunction "2_2") (pintype "passive"))
      (node (ref "C4") (pin "1") (pinfunction "1_1") (pintype "passive"))
      (node (ref "C5") (pin "1") (pinfunction "1_1") (pintype "passive"))
      (node (ref "C6") (pin "1") (pinfunction "1_1") (pintype "passive"))
      (node (ref "C7") (pin "1") (pinfunction "1_1") (pintype "passive"))
      (node (ref "C8") (pin "1") (pinfunction "1_1") (pintype "passive"))
      (node (ref "C9") (pin "1") (pinfunction "1_1") (pintype "passive"))
      (node (ref "D7") (pin "1") (pinfunction "A_1") (pintype "passive"))
      (node (ref "Q1") (pin "2") (pinfunction "E_2") (pintype "passive"))
      (node (ref "R11") (pin "1") (pinfunction "1_1") (pintype "passive"))
      (node (ref "R15") (pin "1") (pinfunction "1_1") (pintype "passive"))
      (node (ref "R18") (pin "2") (pinfunction "2_2") (pintype "passive"))
      (node (ref "R19") (pin "2") (pinfunction "2_2") (pintype "passive"))
      (node (ref "R20") (pin "2") (pinfunction "2_2") (pintype "passive"))
      (node (ref "R22") (pin "2") (pinfunction "2_2") (pintype "passive"))
      (node (ref "R24") (pin "2") (pinfunction "2_2") (pintype "passive"))
      (node (ref "R30") (pin "2") (pinfunction "2_2") (pintype "passive"))
      (node (ref "R33") (pin "2") (pinfunction "2_2") (pintype "passive"))
      (node (ref "R35") (pin "1") (pinfunction "1_1") (pintype "passive"))
      (node (ref "R39") (pin "1") (pinfunction "1_1") (pintype "passive"))
      (node (ref "R40") (pin "1") (pinfunction "1_1") (pintype "passive"))
      (node (ref "R6") (pin "2") (pinfunction "2_2") (pintype "passive"))
      (node (ref "R7") (pin "2") (pinfunction "2_2") (pintype "passive"))
      (node (ref "U1") (pin "C2") (pinfunction "VSS_C2") (pintype "passive"))
      (node (ref "U1") (pin "E4") (pinfunction "VSS_E4") (pintype "passive"))
      (node (ref "U1") (pin "E5") (pinfunction "VSS_E5") (pintype "passive"))
      (node (ref "U1") (pin "E6") (pinfunction "VSS_E6") (pintype "passive"))
      (node (ref "U1") (pin "G1") (pinfunction "VSSA_G1") (pintype "passive"))
      (node (ref "U1") (pin "J1") (pinfunction "VSS_J1") (pintype "passive"))
      (node (ref "U2") (pin "5") (pinfunction "GND_5") (pintype "passive"))
      (node (ref "U3") (pin "5") (pinfunction "GND_5") (pintype "passive"))
      (node (ref "U4") (pin "11") (pinfunction "GND_11") (pintype "passive"))
      (node (ref "U4") (pin "9") (pinfunction "GND_9") (pintype "passive"))
      (node (ref "U5") (pin "1") (pinfunction "GND_1") (pintype "passive"))
      (node (ref "U5") (pin "5") (pinfunction "SDO_5") (pintype "passive"))
      (node (ref "U5") (pin "7") (pinfunction "GND_7") (pintype "passive"))
      (node (ref "U6") (pin "20") (pinfunction "AGND_20") (pintype "passive"))
      (node (ref "U6") (pin "23") (pinfunction "PGND_23") (pintype "passive"))
      (node (ref "U6") (pin "4") (pinfunction "DGND_4") (pintype "passive"))
      (node (ref "U7") (pin "4") (pinfunction "GND_4") (pintype "passive"))
      (node (ref "U7") (pin "9") (pinfunction "EP_9") (pintype "passive"))
      (node (ref "USB1") (pin "A1") (pinfunction "GND_A1") (pintype "passive"))
      (node (ref "USB1") (pin "A12") (pinfunction "GND_A12") (pintype "passive"))
      (node (ref "USB1") (pin "A5") (pinfunction "CC1_A5") (pintype "passive"))
      (node (ref "USB1") (pin "B1") (pinfunction "GND_B1") (pintype "passive"))
      (node (ref "USB1") (pin "B12") (pinfunction "GND_B12") (pintype "passive"))
      (node (ref "USB1") (pin "B5") (pinfunction "CC2_B5") (pintype "passive"))
      (node (ref "X1") (pin "2") (pinfunction "GND_2") (pintype "passive"))
      (node (ref "X2") (pin "2") (pinfunction "2_2") (pintype "passive"))
      (node (ref "X2") (pin "4") (pinfunction "4_4") (pintype "passive"))
    )
    (net (code "72") (name "Net-(C1-Pad2)") (class "Default")
      (node (ref "C1") (pin "2") (pinfunction "2_2") (pintype "passive"))
      (node (ref "R1") (pin "1") (pinfunction "1_1") (pintype "passive"))
    )
    (net (code "73") (name "Net-(C6-Pad2)") (class "Default")
      (node (ref "C6") (pin "2") (pinfunction "2_2") (pintype "passive"))
      (node (ref "U1") (pin "F8") (pinfunction "VCAP_F8") (pintype "passive"))
    )
    (net (code "74") (name "Net-(C7-Pad2)") (class "Default")
      (node (ref "C7") (pin "2") (pinfunction "2_2") (pintype "passive"))
      (node (ref "U1") (pin "E7") (pinfunction "VCAP_E7") (pintype "passive"))
    )
    (net (code "75") (name "Net-(C10-Pad2)") (class "Default")
      (node (ref "C10") (pin "2") (pinfunction "2_2") (pintype "passive"))
      (node (ref "R9") (pin "1") (pinfunction "1_1") (pintype "passive"))
    )
    (net (code "76") (name "Net-(C29-Pad2)") (class "Default")
      (node (ref "C29") (pin "2") (pinfunction "2_2") (pintype "passive"))
      (node (ref "C30") (pin "2") (pinfunction "2_2") (pintype "passive"))
      (node (ref "R32") (pin "1") (pinfunction "1_1") (pintype "passive"))
    )
    (net (code "77") (name "Net-(D1-K)") (class "Default")
      (node (ref "D1") (pin "2") (pinfunction "K_2") (pintype "passive"))
      (node (ref "R19") (pin "1") (pinfunction "1_1") (pintype "passive"))
    )
    (net (code "78") (name "Net-(D2-K)") (class "Default")
      (node (ref "D2") (pin "2") (pinfunction "K_2") (pintype "passive"))
      (node (ref "R20") (pin "1") (pinfunction "1_1") (pintype "passive"))
    )
    (net (code "79") (name "Net-(D3-K)") (class "Default")
      (node (ref "D3") (pin "2") (pinfunction "K_2") (pintype "passive"))
      (node (ref "R22") (pin "1") (pinfunction "1_1") (pintype "passive"))
    )
    (net (code "80") (name "Net-(D4-K)") (class "Default")
      (node (ref "D4") (pin "2") (pinfunction "K_2") (pintype "passive"))
      (node (ref "R23") (pin "1") (pinfunction "1_1") (pintype "passive"))
    )
    (net (code "81") (name "Net-(D5-K)") (class "Default")
      (node (ref "D5") (pin "2") (pinfunction "K_2") (pintype "passive"))
      (node (ref "R24") (pin "1") (pinfunction "1_1") (pintype "passive"))
    )
    (net (code "82") (name "Net-(D6-K)") (class "Default")
      (node (ref "D6") (pin "2") (pinfunction "K_2") (pintype "passive"))
      (node (ref "R25") (pin "1") (pinfunction "1_1") (pintype "passive"))
    )
    (net (code "83") (name "Net-(Q1-B)") (class "Default")
      (node (ref "Q1") (pin "1") (pinfunction "B_1") (pintype "passive"))
      (node (ref "R35") (pin "2") (pinfunction "2_2") (pintype "passive"))
      (node (ref "R37") (pin "1") (pinfunction "1_1") (pintype "passive"))
    )
    (net (code "84") (name "Net-(R3-Pad1)") (class "Default")
      (node (ref "R3") (pin "1") (pinfunction "1_1") (pintype "passive"))
      (node (ref "R5") (pin "2") (pinfunction "2_2") (pintype "passive"))
      (node (ref "R6") (pin "1") (pinfunction "1_1") (pintype "passive"))
    )
    (net (code "85") (name "Net-(R13-Pad1)") (class "Default")
      (node (ref "R13") (pin "1") (pinfunction "1_1") (pintype "passive"))
      (node (ref "R16") (pin "2") (pinfunction "2_2") (pintype "passive"))
      (node (ref "R18") (pin "1") (pinfunction "1_1") (pintype "passive"))
    )
    (net (code "86") (name "Net-(R30-Pad1)") (class "Default")
      (node (ref "R30") (pin "1") (pinfunction "1_1") (pintype "passive"))
      (node (ref "USB1") (pin "S1") (pinfunction "0_S1") (pintype "passive"))
    )
    (net (code "87") (name "Net-(U2-BST)") (class "Default")
      (node (ref "R1") (pin "2") (pinfunction "2_2") (pintype "passive"))
      (node (ref "U2") (pin "4") (pinfunction "BST_4") (pintype "passive"))
    )
    (net (code "88") (name "Net-(U2-EN{slash}SYNC)") (class "Default")
      (node (ref "R2") (pin "1") (pinfunction "1_1") (pintype "passive"))
      (node (ref "U2") (pin "3") (pinfunction "EN/SYNC_3") (pintype "passive"))
    )
    (net (code "89") (name "Net-(U2-FB)") (class "Default")
      (node (ref "R3") (pin "2") (pinfunction "2_2") (pintype "passive"))
      (node (ref "U2") (pin "1") (pinfunction "FB_1") (pintype "passive"))
    )
    (net (code "90") (name "Net-(U2-PG)") (class "Default")
      (node (ref "R4") (pin "2") (pinfunction "2_2") (pintype "passive"))
      (node (ref "U2") (pin "8") (pinfunction "PG_8") (pintype "passive"))
    )
    (net (code "91") (name "Net-(U2-SW)") (class "Default")
      (node (ref "C1") (pin "1") (pinfunction "1_1") (pintype "passive"))
      (node (ref "L1") (pin "1") (pinfunction "1_1") (pintype "passive"))
      (node (ref "U2") (pin "6") (pinfunction "SW_6") (pintype "passive"))
    )
    (net (code "92") (name "Net-(U2-VCC)") (class "Default")
      (node (ref "C8") (pin "2") (pinfunction "2_2") (pintype "passive"))
      (node (ref "R4") (pin "1") (pinfunction "1_1") (pintype "passive"))
      (node (ref "U2") (pin "2") (pinfunction "VCC_2") (pintype "passive"))
    )
    (net (code "93") (name "Net-(U3-BST)") (class "Default")
      (node (ref "R9") (pin "2") (pinfunction "2_2") (pintype "passive"))
      (node (ref "U3") (pin "4") (pinfunction "BST_4") (pintype "passive"))
    )
    (net (code "94") (name "Net-(U3-EN{slash}SYNC)") (class "Default")
      (node (ref "R10") (pin "1") (pinfunction "1_1") (pintype "passive"))
      (node (ref "U3") (pin "3") (pinfunction "EN/SYNC_3") (pintype "passive"))
    )
    (net (code "95") (name "Net-(U3-FB)") (class "Default")
      (node (ref "R13") (pin "2") (pinfunction "2_2") (pintype "passive"))
      (node (ref "U3") (pin "1") (pinfunction "FB_1") (pintype "passive"))
    )
    (net (code "96") (name "Net-(U3-PG)") (class "Default")
      (node (ref "R14") (pin "2") (pinfunction "2_2") (pintype "passive"))
      (node (ref "U3") (pin "8") (pinfunction "PG_8") (pintype "passive"))
    )
    (net (code "97") (name "Net-(U3-SW)") (class "Default")
      (node (ref "C10") (pin "1") (pinfunction "1_1") (pintype "passive"))
      (node (ref "L2") (pin "1") (pinfunction "1_1") (pintype "passive"))
      (node (ref "U3") (pin "6") (pinfunction "SW_6") (pintype "passive"))
    )
    (net (code "98") (name "Net-(U3-VCC)") (class "Default")
      (node (ref "C15") (pin "2") (pinfunction "2_2") (pintype "passive"))
      (node (ref "R14") (pin "1") (pinfunction "1_1") (pintype "passive"))
      (node (ref "U3") (pin "2") (pinfunction "VCC_2") (pintype "passive"))
    )
    (net (code "99") (name "Net-(U4-C1)") (class "Default")
      (node (ref "C25") (pin "1") (pinfunction "1_1") (pintype "passive"))
      (node (ref "U4") (pin "10") (pinfunction "C1_10") (pintype "passive"))
    )
    (net (code "100") (name "Net-(U4-SETC)") (class "Default")
      (node (ref "C27") (pin "2") (pinfunction "2_2") (pintype "passive"))
      (node (ref "U4") (pin "12") (pinfunction "SETC_12") (pintype "passive"))
    )
    (net (code "101") (name "Net-(U4-SETP)") (class "Default")
      (node (ref "C27") (pin "1") (pinfunction "1_1") (pintype "passive"))
      (node (ref "U4") (pin "8") (pinfunction "SETP_8") (pintype "passive"))
    )
    (net (code "102") (name "Net-(U6-CLKIN)") (class "Default")
      (node (ref "U6") (pin "5") (pinfunction "CLKIN_5") (pintype "passive"))
      (node (ref "X2") (pin "3") (pinfunction "3_3") (pintype "passive"))
    )
    (net (code "103") (name "Net-(U6-SAG)") (class "Default")
      (node (ref "C30") (pin "1") (pinfunction "1_1") (pintype "passive"))
      (node (ref "U6") (pin "25") (pinfunction "SAG_25") (pintype "passive"))
    )
    (net (code "104") (name "Net-(U6-VIN)") (class "Default")
      (node (ref "C31") (pin "1") (pinfunction "1_1") (pintype "passive"))
      (node (ref "U6") (pin "22") (pinfunction "VIN_22") (pintype "passive"))
    )
    (net (code "105") (name "Net-(U6-VOUT)") (class "Default")
      (node (ref "C29") (pin "1") (pinfunction "1_1") (pintype "passive"))
      (node (ref "U6") (pin "26") (pinfunction "VOUT_26") (pintype "passive"))
    )
    (net (code "106") (name "Net-(U6-XFB)") (class "Default")
      (node (ref "U6") (pin "6") (pinfunction "XFB_6") (pintype "passive"))
      (node (ref "X2") (pin "1") (pinfunction "1_1") (pintype "passive"))
    )
    (net (code "107") (name "USB_5V") (class "Default")
      (node (ref "D2") (pin "1") (pinfunction "A_1") (pintype "passive"))
      (node (ref "R38") (pin "1") (pinfunction "1_1") (pintype "passive"))
      (node (ref "USB1") (pin "A4") (pinfunction "VBUS_A4") (pintype "passive"))
      (node (ref "USB1") (pin "A9") (pinfunction "VBUS_A9") (pintype "passive"))
      (node (ref "USB1") (pin "B4") (pinfunction "VBUS_B4") (pintype "passive"))
      (node (ref "USB1") (pin "B9") (pinfunction "VBUS_B9") (pintype "passive"))
    )
    (net (code "108") (name "VBAT") (class "Default")
      (node (ref "C13") (pin "2") (pinfunction "2_2") (pintype "passive"))
      (node (ref "C14") (pin "2") (pinfunction "2_2") (pintype "passive"))
      (node (ref "C4") (pin "2") (pinfunction "2_2") (pintype "passive"))
      (node (ref "C5") (pin "2") (pinfunction "2_2") (pintype "passive"))
      (node (ref "R10") (pin "2") (pinfunction "2_2") (pintype "passive"))
      (node (ref "R12") (pin "2") (pinfunction "2_2") (pintype "passive"))
      (node (ref "R2") (pin "2") (pinfunction "2_2") (pintype "passive"))
      (node (ref "U2") (pin "7") (pinfunction "VIN_7") (pintype "passive"))
      (node (ref "U3") (pin "7") (pinfunction "VIN_7") (pintype "passive"))
    )
    (net (code "109") (name "VCCA") (class "Default")
      (node (ref "C19") (pin "1") (pinfunction "1_1") (pintype "passive"))
      (node (ref "C20") (pin "1") (pinfunction "1_1") (pintype "passive"))
      (node (ref "C21") (pin "1") (pinfunction "1_1") (pintype "passive"))
      (node (ref "R21") (pin "2") (pinfunction "2_2") (pintype "passive"))
      (node (ref "R8") (pin "1") (pinfunction "1_1") (pintype "passive"))
      (node (ref "U1") (pin "B2") (pinfunction "VBAT_B2") (pintype "passive"))
      (node (ref "U1") (pin "D2") (pinfunction "VDD_D2") (pintype "passive"))
      (node (ref "U1") (pin "F4") (pinfunction "VDDLDO_F4") (pintype "passive"))
      (node (ref "U1") (pin "F5") (pinfunction "VDD_F5") (pintype "passive"))
      (node (ref "U1") (pin "F6") (pinfunction "33USB_F6") (pintype "passive"))
      (node (ref "U1") (pin "F7") (pinfunction "PDR_ON_F7") (pintype "passive"))
      (node (ref "U1") (pin "H1") (pinfunction "VDDA_H1") (pintype "passive"))
      (node (ref "U1") (pin "K1") (pinfunction "VDD_K1") (pintype "passive"))
    )
    (net (code "110") (name "unconnected-(SW1-Pad3)") (class "Default")
      (node (ref "SW1") (pin "3") (pinfunction "3_3") (pintype "passive+no_connect"))
    )
    (net (code "111") (name "unconnected-(SW1-Pad4)") (class "Default")
      (node (ref "SW1") (pin "4") (pinfunction "4_4") (pintype "passive+no_connect"))
    )
    (net (code "112") (name "unconnected-(U1A-PA8-PadD9)") (class "Default")
      (node (ref "U1") (pin "D9") (pinfunction "PA8_D9") (pintype "passive"))
    )
    (net (code "113") (name "unconnected-(U1A-PB2-PadG5)") (class "Default")
      (node (ref "U1") (pin "G5") (pinfunction "PB2_G5") (pintype "passive"))
    )
    (net (code "114") (name "unconnected-(U1A-PB8-PadB4)") (class "Default")
      (node (ref "U1") (pin "B4") (pinfunction "PB8_B4") (pintype "passive"))
    )
    (net (code "115") (name "unconnected-(U1A-PB9-PadA4)") (class "Default")
      (node (ref "U1") (pin "A4") (pinfunction "PB9_A4") (pintype "passive"))
    )
    (net (code "116") (name "unconnected-(U1A-PC2_C-PadE2)") (class "Default")
      (node (ref "U1") (pin "E2") (pinfunction "PC2_C_E2") (pintype "passive"))
    )
    (net (code "117") (name "unconnected-(U1A-PC3_C-PadF3)") (class "Default")
      (node (ref "U1") (pin "F3") (pinfunction "PC3_C_F3") (pintype "passive"))
    )
    (net (code "118") (name "unconnected-(U1A-PC12-PadC8)") (class "Default")
      (node (ref "U1") (pin "C8") (pinfunction "PC12_C8") (pintype "passive"))
    )
    (net (code "119") (name "unconnected-(U1A-PC13-PadA2)") (class "Default")
      (node (ref "U1") (pin "A2") (pinfunction "PC13_A2") (pintype "passive"))
    )
    (net (code "120") (name "unconnected-(U1A-PC14-OSC32_IN-PadA1)") (class "Default")
      (node (ref "U1") (pin "A1") (pinfunction "PC14-OSC32_IN_A1") (pintype "passive"))
    )
    (net (code "121") (name "unconnected-(U1A-PC15-OSC32_OUT-PadB1)") (class "Default")
      (node (ref "U1") (pin "B1") (pinfunction "PC15-OSC32_OUT_B1") (pintype "passive"))
    )
    (net (code "122") (name "unconnected-(U1A-PD0-PadD8)") (class "Default")
      (node (ref "U1") (pin "D8") (pinfunction "PD0_D8") (pintype "passive"))
    )
    (net (code "123") (name "unconnected-(U1A-PD1-PadE8)") (class "Default")
      (node (ref "U1") (pin "E8") (pinfunction "PD1_E8") (pintype "passive"))
    )
    (net (code "124") (name "unconnected-(U1A-PD2-PadB7)") (class "Default")
      (node (ref "U1") (pin "B7") (pinfunction "PD2_B7") (pintype "passive"))
    )
    (net (code "125") (name "unconnected-(U1A-PD3-PadC7)") (class "Default")
      (node (ref "U1") (pin "C7") (pinfunction "PD3_C7") (pintype "passive"))
    )
    (net (code "126") (name "unconnected-(U1A-PD4-PadD7)") (class "Default")
      (node (ref "U1") (pin "D7") (pinfunction "PD4_D7") (pintype "passive"))
    )
    (net (code "127") (name "unconnected-(U1A-PD7-PadD6)") (class "Default")
      (node (ref "U1") (pin "D6") (pinfunction "PD7_D6") (pintype "passive"))
    )
    (net (code "128") (name "unconnected-(U1A-PD8-PadK9)") (class "Default")
      (node (ref "U1") (pin "K9") (pinfunction "PD8_K9") (pintype "passive"))
    )
    (net (code "129") (name "unconnected-(U1A-PD10-PadH9)") (class "Default")
      (node (ref "U1") (pin "H9") (pinfunction "PD10_H9") (pintype "passive"))
    )
    (net (code "130") (name "unconnected-(U1A-PD11-PadG9)") (class "Default")
      (node (ref "U1") (pin "G9") (pinfunction "PD11_G9") (pintype "passive"))
    )
    (net (code "131") (name "unconnected-(U1A-PE0-PadD4)") (class "Default")
      (node (ref "U1") (pin "D4") (pinfunction "PE0_D4") (pintype "passive"))
    )
    (net (code "132") (name "unconnected-(U1A-PE1-PadC4)") (class "Default")
      (node (ref "U1") (pin "C4") (pinfunction "PE1_C4") (pintype "passive"))
    )
    (net (code "133") (name "unconnected-(U1A-PE2-PadA3)") (class "Default")
      (node (ref "U1") (pin "A3") (pinfunction "PE2_A3") (pintype "passive"))
    )
    (net (code "134") (name "unconnected-(U1A-PE3-PadB3)") (class "Default")
      (node (ref "U1") (pin "B3") (pinfunction "PE3_B3") (pintype "passive"))
    )
    (net (code "135") (name "unconnected-(U1A-PE4-PadC3)") (class "Default")
      (node (ref "U1") (pin "C3") (pinfunction "PE4_C3") (pintype "passive"))
    )
    (net (code "136") (name "unconnected-(U1A-PE10-PadG6)") (class "Default")
      (node (ref "U1") (pin "G6") (pinfunction "PE10_G6") (pintype "passive"))
    )
    (net (code "137") (name "unconnected-(U1A-PE14-PadG7)") (class "Default")
      (node (ref "U1") (pin "G7") (pinfunction "PE14_G7") (pintype "passive"))
    )
    (net (code "138") (name "unconnected-(U1A-PE15-PadH7)") (class "Default")
      (node (ref "U1") (pin "H7") (pinfunction "PE15_H7") (pintype "passive"))
    )
    (net (code "139") (name "unconnected-(U4-NC-Pad3)") (class "Default")
      (node (ref "U4") (pin "3") (pinfunction "NC_3") (pintype "passive+no_connect"))
    )
    (net (code "140") (name "unconnected-(U4-NC-Pad5)") (class "Default")
      (node (ref "U4") (pin "5") (pinfunction "NC_5") (pintype "passive+no_connect"))
    )
    (net (code "141") (name "unconnected-(U4-NC-Pad6)") (class "Default")
      (node (ref "U4") (pin "6") (pinfunction "NC_6") (pintype "passive+no_connect"))
    )
    (net (code "142") (name "unconnected-(U4-NC-Pad7)") (class "Default")
      (node (ref "U4") (pin "7") (pinfunction "NC_7") (pintype "passive+no_connect"))
    )
    (net (code "143") (name "unconnected-(U4-NC-Pad14)") (class "Default")
      (node (ref "U4") (pin "14") (pinfunction "NC_14") (pintype "passive+no_connect"))
    )
    (net (code "144") (name "unconnected-(U6-CLKOUT-Pad7)") (class "Default")
      (node (ref "U6") (pin "7") (pinfunction "CLKOUT_7") (pintype "passive"))
    )
    (net (code "145") (name "unconnected-(U6-NC-Pad1)") (class "Default")
      (node (ref "U6") (pin "1") (pinfunction "NC_1") (pintype "passive+no_connect"))
    )
    (net (code "146") (name "unconnected-(U6-NC-Pad2)") (class "Default")
      (node (ref "U6") (pin "2") (pinfunction "NC_2") (pintype "passive+no_connect"))
    )
    (net (code "147") (name "unconnected-(U6-NC-Pad13)") (class "Default")
      (node (ref "U6") (pin "13") (pinfunction "NC_13") (pintype "passive+no_connect"))
    )
    (net (code "148") (name "unconnected-(U6-NC-Pad14)") (class "Default")
      (node (ref "U6") (pin "14") (pinfunction "NC_14") (pintype "passive+no_connect"))
    )
    (net (code "149") (name "unconnected-(U6-NC-Pad15)") (class "Default")
      (node (ref "U6") (pin "15") (pinfunction "NC_15") (pintype "passive+no_connect"))
    )
    (net (code "150") (name "unconnected-(U6-NC-Pad16)") (class "Default")
      (node (ref "U6") (pin "16") (pinfunction "NC_16") (pintype "passive+no_connect"))
    )
    (net (code "151") (name "unconnected-(U6-NC-Pad27)") (class "Default")
      (node (ref "U6") (pin "27") (pinfunction "NC_27") (pintype "passive+no_connect"))
    )
    (net (code "152") (name "unconnected-(U6-NC-Pad28)") (class "Default")
      (node (ref "U6") (pin "28") (pinfunction "NC_28") (pintype "passive+no_connect"))
    )
    (net (code "153") (name "unconnected-(USB1-0-PadS2)") (class "Default")
      (node (ref "USB1") (pin "S2") (pinfunction "0_S2") (pintype "passive+no_connect"))
    )
    (net (code "154") (name "unconnected-(USB1-0-PadS3)") (class "Default")
      (node (ref "USB1") (pin "S3") (pinfunction "0_S3") (pintype "passive+no_connect"))
    )
    (net (code "155") (name "unconnected-(USB1-0-PadS4)") (class "Default")
      (node (ref "USB1") (pin "S4") (pinfunction "0_S4") (pintype "passive+no_connect"))
    )
    (net (code "156") (name "unconnected-(USB1-SBU1-PadA8)") (class "Default")
      (node (ref "USB1") (pin "A8") (pinfunction "SBU1_A8") (pintype "passive+no_connect"))
    )
    (net (code "157") (name "unconnected-(USB1-SBU2-PadB8)") (class "Default")
      (node (ref "USB1") (pin "B8") (pinfunction "SBU2_B8") (pintype "passive+no_connect"))
    )
  )
)
